# BottomSide.net
KiCad netlist of a schematic drawn in Altium Designer
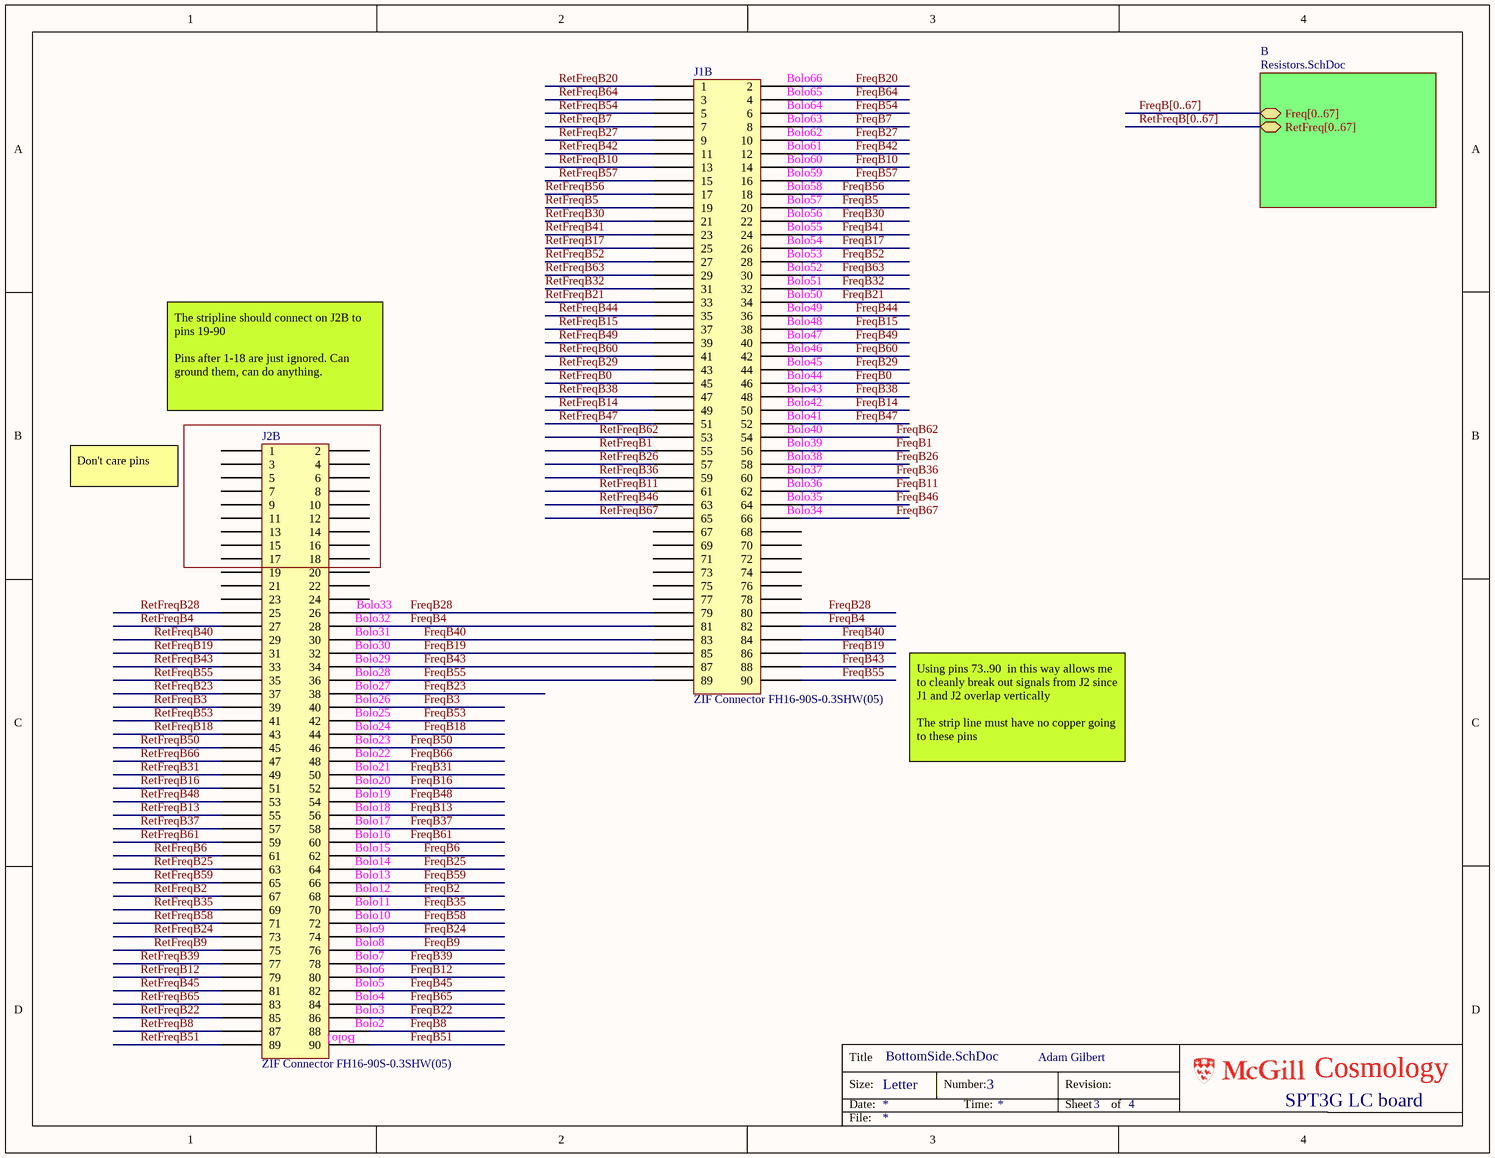
[diagram p0: BottomSide.SchDoc]

(export (version "E")
  (design (tool "Eeschema 10.0.6"))
  (components
    (comp (ref "J1B")
      (value "ZIF Connector FH16-90S-0.3SHW(05)")
      (footprint "LCBoard_ZIFCon")
      (libsource (lib "SPT3G_LCBoard") (part "LCboard_FH16-90S-0.3SHW(05)"))
    )
    (comp (ref "J2B")
      (value "ZIF Connector FH16-90S-0.3SHW(05)")
      (footprint "LCBoard_ZIFCon")
      (libsource (lib "SPT3G_LCBoard") (part "LCboard_FH16-90S-0.3SHW(05)"))
    )
  )
  (nets
    (net (code "5") (name "/FreqB0") (class "Default")
      (node (ref "J1B") (pin "46") (pinfunction "46_46") (pintype "passive"))
    )
    (net (code "6") (name "/FreqB1") (class "Default")
      (node (ref "J1B") (pin "56") (pinfunction "56_56") (pintype "passive"))
    )
    (net (code "7") (name "/FreqB2") (class "Default")
      (node (ref "J2B") (pin "68") (pinfunction "68_68") (pintype "passive"))
    )
    (net (code "8") (name "/FreqB3") (class "Default")
      (node (ref "J2B") (pin "40") (pinfunction "40_40") (pintype "passive"))
    )
    (net (code "9") (name "/FreqB4") (class "Default")
      (node (ref "J1B") (pin "81") (pinfunction "81_81") (pintype "passive"))
      (node (ref "J1B") (pin "82") (pinfunction "82_82") (pintype "passive"))
      (node (ref "J2B") (pin "28") (pinfunction "28_28") (pintype "passive"))
    )
    (net (code "10") (name "/FreqB5") (class "Default")
      (node (ref "J1B") (pin "20") (pinfunction "20_20") (pintype "passive"))
    )
    (net (code "11") (name "/FreqB6") (class "Default")
      (node (ref "J2B") (pin "62") (pinfunction "62_62") (pintype "passive"))
    )
    (net (code "12") (name "/FreqB7") (class "Default")
      (node (ref "J1B") (pin "8") (pinfunction "8_8") (pintype "passive"))
    )
    (net (code "13") (name "/FreqB8") (class "Default")
      (node (ref "J2B") (pin "88") (pinfunction "88_88") (pintype "passive"))
    )
    (net (code "14") (name "/FreqB9") (class "Default")
      (node (ref "J2B") (pin "76") (pinfunction "76_76") (pintype "passive"))
    )
    (net (code "15") (name "/FreqB10") (class "Default")
      (node (ref "J1B") (pin "14") (pinfunction "14_14") (pintype "passive"))
    )
    (net (code "16") (name "/FreqB11") (class "Default")
      (node (ref "J1B") (pin "62") (pinfunction "62_62") (pintype "passive"))
    )
    (net (code "17") (name "/FreqB12") (class "Default")
      (node (ref "J2B") (pin "80") (pinfunction "80_80") (pintype "passive"))
    )
    (net (code "18") (name "/FreqB13") (class "Default")
      (node (ref "J2B") (pin "56") (pinfunction "56_56") (pintype "passive"))
    )
    (net (code "19") (name "/FreqB14") (class "Default")
      (node (ref "J1B") (pin "50") (pinfunction "50_50") (pintype "passive"))
    )
    (net (code "20") (name "/FreqB15") (class "Default")
      (node (ref "J1B") (pin "38") (pinfunction "38_38") (pintype "passive"))
    )
    (net (code "21") (name "/FreqB16") (class "Default")
      (node (ref "J2B") (pin "52") (pinfunction "52_52") (pintype "passive"))
    )
    (net (code "22") (name "/FreqB17") (class "Default")
      (node (ref "J1B") (pin "26") (pinfunction "26_26") (pintype "passive"))
    )
    (net (code "23") (name "/FreqB18") (class "Default")
      (node (ref "J2B") (pin "44") (pinfunction "44_44") (pintype "passive"))
    )
    (net (code "24") (name "/FreqB19") (class "Default")
      (node (ref "J1B") (pin "85") (pinfunction "85_85") (pintype "passive"))
      (node (ref "J1B") (pin "86") (pinfunction "86_86") (pintype "passive"))
      (node (ref "J2B") (pin "32") (pinfunction "32_32") (pintype "passive"))
    )
    (net (code "25") (name "/FreqB20") (class "Default")
      (node (ref "J1B") (pin "2") (pinfunction "2_2") (pintype "passive"))
    )
    (net (code "26") (name "/FreqB21") (class "Default")
      (node (ref "J1B") (pin "34") (pinfunction "34_34") (pintype "passive"))
    )
    (net (code "27") (name "/FreqB22") (class "Default")
      (node (ref "J2B") (pin "86") (pinfunction "86_86") (pintype "passive"))
    )
    (net (code "28") (name "/FreqB23") (class "Default")
      (node (ref "J2B") (pin "38") (pinfunction "38_38") (pintype "passive"))
    )
    (net (code "29") (name "/FreqB24") (class "Default")
      (node (ref "J2B") (pin "74") (pinfunction "74_74") (pintype "passive"))
    )
    (net (code "30") (name "/FreqB25") (class "Default")
      (node (ref "J2B") (pin "64") (pinfunction "64_64") (pintype "passive"))
    )
    (net (code "31") (name "/FreqB26") (class "Default")
      (node (ref "J1B") (pin "58") (pinfunction "58_58") (pintype "passive"))
    )
    (net (code "32") (name "/FreqB27") (class "Default")
      (node (ref "J1B") (pin "10") (pinfunction "10_10") (pintype "passive"))
    )
    (net (code "33") (name "/FreqB28") (class "Default")
      (node (ref "J1B") (pin "79") (pinfunction "79_79") (pintype "passive"))
      (node (ref "J1B") (pin "80") (pinfunction "80_80") (pintype "passive"))
      (node (ref "J2B") (pin "26") (pinfunction "26_26") (pintype "passive"))
    )
    (net (code "34") (name "/FreqB29") (class "Default")
      (node (ref "J1B") (pin "44") (pinfunction "44_44") (pintype "passive"))
    )
    (net (code "35") (name "/FreqB30") (class "Default")
      (node (ref "J1B") (pin "22") (pinfunction "22_22") (pintype "passive"))
    )
    (net (code "36") (name "/FreqB31") (class "Default")
      (node (ref "J2B") (pin "50") (pinfunction "50_50") (pintype "passive"))
    )
    (net (code "37") (name "/FreqB32") (class "Default")
      (node (ref "J1B") (pin "32") (pinfunction "32_32") (pintype "passive"))
    )
    (net (code "38") (name "/FreqB35") (class "Default")
      (node (ref "J2B") (pin "70") (pinfunction "70_70") (pintype "passive"))
    )
    (net (code "39") (name "/FreqB36") (class "Default")
      (node (ref "J1B") (pin "60") (pinfunction "60_60") (pintype "passive"))
    )
    (net (code "40") (name "/FreqB37") (class "Default")
      (node (ref "J2B") (pin "58") (pinfunction "58_58") (pintype "passive"))
    )
    (net (code "41") (name "/FreqB38") (class "Default")
      (node (ref "J1B") (pin "48") (pinfunction "48_48") (pintype "passive"))
    )
    (net (code "42") (name "/FreqB39") (class "Default")
      (node (ref "J2B") (pin "78") (pinfunction "78_78") (pintype "passive"))
    )
    (net (code "43") (name "/FreqB40") (class "Default")
      (node (ref "J1B") (pin "83") (pinfunction "83_83") (pintype "passive"))
      (node (ref "J1B") (pin "84") (pinfunction "84_84") (pintype "passive"))
      (node (ref "J2B") (pin "30") (pinfunction "30_30") (pintype "passive"))
    )
    (net (code "44") (name "/FreqB41") (class "Default")
      (node (ref "J1B") (pin "24") (pinfunction "24_24") (pintype "passive"))
    )
    (net (code "45") (name "/FreqB42") (class "Default")
      (node (ref "J1B") (pin "12") (pinfunction "12_12") (pintype "passive"))
    )
    (net (code "46") (name "/FreqB43") (class "Default")
      (node (ref "J1B") (pin "87") (pinfunction "87_87") (pintype "passive"))
      (node (ref "J1B") (pin "88") (pinfunction "88_88") (pintype "passive"))
      (node (ref "J2B") (pin "34") (pinfunction "34_34") (pintype "passive"))
    )
    (net (code "47") (name "/FreqB44") (class "Default")
      (node (ref "J1B") (pin "36") (pinfunction "36_36") (pintype "passive"))
    )
    (net (code "48") (name "/FreqB45") (class "Default")
      (node (ref "J2B") (pin "82") (pinfunction "82_82") (pintype "passive"))
    )
    (net (code "49") (name "/FreqB46") (class "Default")
      (node (ref "J1B") (pin "64") (pinfunction "64_64") (pintype "passive"))
    )
    (net (code "50") (name "/FreqB47") (class "Default")
      (node (ref "J1B") (pin "52") (pinfunction "52_52") (pintype "passive"))
    )
    (net (code "51") (name "/FreqB48") (class "Default")
      (node (ref "J2B") (pin "54") (pinfunction "54_54") (pintype "passive"))
    )
    (net (code "52") (name "/FreqB49") (class "Default")
      (node (ref "J1B") (pin "40") (pinfunction "40_40") (pintype "passive"))
    )
    (net (code "53") (name "/FreqB50") (class "Default")
      (node (ref "J2B") (pin "46") (pinfunction "46_46") (pintype "passive"))
    )
    (net (code "54") (name "/FreqB51") (class "Default")
      (node (ref "J2B") (pin "90") (pinfunction "90_90") (pintype "passive"))
    )
    (net (code "55") (name "/FreqB52") (class "Default")
      (node (ref "J1B") (pin "28") (pinfunction "28_28") (pintype "passive"))
    )
    (net (code "56") (name "/FreqB53") (class "Default")
      (node (ref "J2B") (pin "42") (pinfunction "42_42") (pintype "passive"))
    )
    (net (code "57") (name "/FreqB54") (class "Default")
      (node (ref "J1B") (pin "6") (pinfunction "6_6") (pintype "passive"))
    )
    (net (code "58") (name "/FreqB55") (class "Default")
      (node (ref "J1B") (pin "89") (pinfunction "89_89") (pintype "passive"))
      (node (ref "J1B") (pin "90") (pinfunction "90_90") (pintype "passive"))
      (node (ref "J2B") (pin "36") (pinfunction "36_36") (pintype "passive"))
    )
    (net (code "59") (name "/FreqB56") (class "Default")
      (node (ref "J1B") (pin "18") (pinfunction "18_18") (pintype "passive"))
    )
    (net (code "60") (name "/FreqB57") (class "Default")
      (node (ref "J1B") (pin "16") (pinfunction "16_16") (pintype "passive"))
    )
    (net (code "61") (name "/FreqB58") (class "Default")
      (node (ref "J2B") (pin "72") (pinfunction "72_72") (pintype "passive"))
    )
    (net (code "62") (name "/FreqB59") (class "Default")
      (node (ref "J2B") (pin "66") (pinfunction "66_66") (pintype "passive"))
    )
    (net (code "63") (name "/FreqB60") (class "Default")
      (node (ref "J1B") (pin "42") (pinfunction "42_42") (pintype "passive"))
    )
    (net (code "64") (name "/FreqB61") (class "Default")
      (node (ref "J2B") (pin "60") (pinfunction "60_60") (pintype "passive"))
    )
    (net (code "65") (name "/FreqB62") (class "Default")
      (node (ref "J1B") (pin "54") (pinfunction "54_54") (pintype "passive"))
    )
    (net (code "66") (name "/FreqB63") (class "Default")
      (node (ref "J1B") (pin "30") (pinfunction "30_30") (pintype "passive"))
    )
    (net (code "67") (name "/FreqB64") (class "Default")
      (node (ref "J1B") (pin "4") (pinfunction "4_4") (pintype "passive"))
    )
    (net (code "68") (name "/FreqB65") (class "Default")
      (node (ref "J2B") (pin "84") (pinfunction "84_84") (pintype "passive"))
    )
    (net (code "69") (name "/FreqB66") (class "Default")
      (node (ref "J2B") (pin "48") (pinfunction "48_48") (pintype "passive"))
    )
    (net (code "70") (name "/FreqB67") (class "Default")
      (node (ref "J1B") (pin "66") (pinfunction "66_66") (pintype "passive"))
    )
    (net (code "72") (name "/RetFreqB0") (class "Default")
      (node (ref "J1B") (pin "45") (pinfunction "45_45") (pintype "passive"))
    )
    (net (code "73") (name "/RetFreqB1") (class "Default")
      (node (ref "J1B") (pin "55") (pinfunction "55_55") (pintype "passive"))
    )
    (net (code "74") (name "/RetFreqB2") (class "Default")
      (node (ref "J2B") (pin "67") (pinfunction "67_67") (pintype "passive"))
    )
    (net (code "75") (name "/RetFreqB3") (class "Default")
      (node (ref "J2B") (pin "39") (pinfunction "39_39") (pintype "passive"))
    )
    (net (code "76") (name "/RetFreqB4") (class "Default")
      (node (ref "J2B") (pin "27") (pinfunction "27_27") (pintype "passive"))
    )
    (net (code "77") (name "/RetFreqB5") (class "Default")
      (node (ref "J1B") (pin "19") (pinfunction "19_19") (pintype "passive"))
    )
    (net (code "78") (name "/RetFreqB6") (class "Default")
      (node (ref "J2B") (pin "61") (pinfunction "61_61") (pintype "passive"))
    )
    (net (code "79") (name "/RetFreqB7") (class "Default")
      (node (ref "J1B") (pin "7") (pinfunction "7_7") (pintype "passive"))
    )
    (net (code "80") (name "/RetFreqB8") (class "Default")
      (node (ref "J2B") (pin "87") (pinfunction "87_87") (pintype "passive"))
    )
    (net (code "81") (name "/RetFreqB9") (class "Default")
      (node (ref "J2B") (pin "75") (pinfunction "75_75") (pintype "passive"))
    )
    (net (code "82") (name "/RetFreqB10") (class "Default")
      (node (ref "J1B") (pin "13") (pinfunction "13_13") (pintype "passive"))
    )
    (net (code "83") (name "/RetFreqB11") (class "Default")
      (node (ref "J1B") (pin "61") (pinfunction "61_61") (pintype "passive"))
    )
    (net (code "84") (name "/RetFreqB12") (class "Default")
      (node (ref "J2B") (pin "79") (pinfunction "79_79") (pintype "passive"))
    )
    (net (code "85") (name "/RetFreqB13") (class "Default")
      (node (ref "J2B") (pin "55") (pinfunction "55_55") (pintype "passive"))
    )
    (net (code "86") (name "/RetFreqB14") (class "Default")
      (node (ref "J1B") (pin "49") (pinfunction "49_49") (pintype "passive"))
    )
    (net (code "87") (name "/RetFreqB15") (class "Default")
      (node (ref "J1B") (pin "37") (pinfunction "37_37") (pintype "passive"))
    )
    (net (code "88") (name "/RetFreqB16") (class "Default")
      (node (ref "J2B") (pin "51") (pinfunction "51_51") (pintype "passive"))
    )
    (net (code "89") (name "/RetFreqB17") (class "Default")
      (node (ref "J1B") (pin "25") (pinfunction "25_25") (pintype "passive"))
    )
    (net (code "90") (name "/RetFreqB18") (class "Default")
      (node (ref "J2B") (pin "43") (pinfunction "43_43") (pintype "passive"))
    )
    (net (code "91") (name "/RetFreqB19") (class "Default")
      (node (ref "J2B") (pin "31") (pinfunction "31_31") (pintype "passive"))
    )
    (net (code "92") (name "/RetFreqB20") (class "Default")
      (node (ref "J1B") (pin "1") (pinfunction "1_1") (pintype "passive"))
    )
    (net (code "93") (name "/RetFreqB21") (class "Default")
      (node (ref "J1B") (pin "33") (pinfunction "33_33") (pintype "passive"))
    )
    (net (code "94") (name "/RetFreqB22") (class "Default")
      (node (ref "J2B") (pin "85") (pinfunction "85_85") (pintype "passive"))
    )
    (net (code "95") (name "/RetFreqB23") (class "Default")
      (node (ref "J2B") (pin "37") (pinfunction "37_37") (pintype "passive"))
    )
    (net (code "96") (name "/RetFreqB24") (class "Default")
      (node (ref "J2B") (pin "73") (pinfunction "73_73") (pintype "passive"))
    )
    (net (code "97") (name "/RetFreqB25") (class "Default")
      (node (ref "J2B") (pin "63") (pinfunction "63_63") (pintype "passive"))
    )
    (net (code "98") (name "/RetFreqB26") (class "Default")
      (node (ref "J1B") (pin "57") (pinfunction "57_57") (pintype "passive"))
    )
    (net (code "99") (name "/RetFreqB27") (class "Default")
      (node (ref "J1B") (pin "9") (pinfunction "9_9") (pintype "passive"))
    )
    (net (code "100") (name "/RetFreqB28") (class "Default")
      (node (ref "J2B") (pin "25") (pinfunction "25_25") (pintype "passive"))
    )
    (net (code "101") (name "/RetFreqB29") (class "Default")
      (node (ref "J1B") (pin "43") (pinfunction "43_43") (pintype "passive"))
    )
    (net (code "102") (name "/RetFreqB30") (class "Default")
      (node (ref "J1B") (pin "21") (pinfunction "21_21") (pintype "passive"))
    )
    (net (code "103") (name "/RetFreqB31") (class "Default")
      (node (ref "J2B") (pin "49") (pinfunction "49_49") (pintype "passive"))
    )
    (net (code "104") (name "/RetFreqB32") (class "Default")
      (node (ref "J1B") (pin "31") (pinfunction "31_31") (pintype "passive"))
    )
    (net (code "105") (name "/RetFreqB35") (class "Default")
      (node (ref "J2B") (pin "69") (pinfunction "69_69") (pintype "passive"))
    )
    (net (code "106") (name "/RetFreqB36") (class "Default")
      (node (ref "J1B") (pin "59") (pinfunction "59_59") (pintype "passive"))
    )
    (net (code "107") (name "/RetFreqB37") (class "Default")
      (node (ref "J2B") (pin "57") (pinfunction "57_57") (pintype "passive"))
    )
    (net (code "108") (name "/RetFreqB38") (class "Default")
      (node (ref "J1B") (pin "47") (pinfunction "47_47") (pintype "passive"))
    )
    (net (code "109") (name "/RetFreqB39") (class "Default")
      (node (ref "J2B") (pin "77") (pinfunction "77_77") (pintype "passive"))
    )
    (net (code "110") (name "/RetFreqB40") (class "Default")
      (node (ref "J2B") (pin "29") (pinfunction "29_29") (pintype "passive"))
    )
    (net (code "111") (name "/RetFreqB41") (class "Default")
      (node (ref "J1B") (pin "23") (pinfunction "23_23") (pintype "passive"))
    )
    (net (code "112") (name "/RetFreqB42") (class "Default")
      (node (ref "J1B") (pin "11") (pinfunction "11_11") (pintype "passive"))
    )
    (net (code "113") (name "/RetFreqB43") (class "Default")
      (node (ref "J2B") (pin "33") (pinfunction "33_33") (pintype "passive"))
    )
    (net (code "114") (name "/RetFreqB44") (class "Default")
      (node (ref "J1B") (pin "35") (pinfunction "35_35") (pintype "passive"))
    )
    (net (code "115") (name "/RetFreqB45") (class "Default")
      (node (ref "J2B") (pin "81") (pinfunction "81_81") (pintype "passive"))
    )
    (net (code "116") (name "/RetFreqB46") (class "Default")
      (node (ref "J1B") (pin "63") (pinfunction "63_63") (pintype "passive"))
    )
    (net (code "117") (name "/RetFreqB47") (class "Default")
      (node (ref "J1B") (pin "51") (pinfunction "51_51") (pintype "passive"))
    )
    (net (code "118") (name "/RetFreqB48") (class "Default")
      (node (ref "J2B") (pin "53") (pinfunction "53_53") (pintype "passive"))
    )
    (net (code "119") (name "/RetFreqB49") (class "Default")
      (node (ref "J1B") (pin "39") (pinfunction "39_39") (pintype "passive"))
    )
    (net (code "120") (name "/RetFreqB50") (class "Default")
      (node (ref "J2B") (pin "45") (pinfunction "45_45") (pintype "passive"))
    )
    (net (code "121") (name "/RetFreqB51") (class "Default")
      (node (ref "J2B") (pin "89") (pinfunction "89_89") (pintype "passive"))
    )
    (net (code "122") (name "/RetFreqB52") (class "Default")
      (node (ref "J1B") (pin "27") (pinfunction "27_27") (pintype "passive"))
    )
    (net (code "123") (name "/RetFreqB53") (class "Default")
      (node (ref "J2B") (pin "41") (pinfunction "41_41") (pintype "passive"))
    )
    (net (code "124") (name "/RetFreqB54") (class "Default")
      (node (ref "J1B") (pin "5") (pinfunction "5_5") (pintype "passive"))
    )
    (net (code "125") (name "/RetFreqB55") (class "Default")
      (node (ref "J2B") (pin "35") (pinfunction "35_35") (pintype "passive"))
    )
    (net (code "126") (name "/RetFreqB56") (class "Default")
      (node (ref "J1B") (pin "17") (pinfunction "17_17") (pintype "passive"))
    )
    (net (code "127") (name "/RetFreqB57") (class "Default")
      (node (ref "J1B") (pin "15") (pinfunction "15_15") (pintype "passive"))
    )
    (net (code "128") (name "/RetFreqB58") (class "Default")
      (node (ref "J2B") (pin "71") (pinfunction "71_71") (pintype "passive"))
    )
    (net (code "129") (name "/RetFreqB59") (class "Default")
      (node (ref "J2B") (pin "65") (pinfunction "65_65") (pintype "passive"))
    )
    (net (code "130") (name "/RetFreqB60") (class "Default")
      (node (ref "J1B") (pin "41") (pinfunction "41_41") (pintype "passive"))
    )
    (net (code "131") (name "/RetFreqB61") (class "Default")
      (node (ref "J2B") (pin "59") (pinfunction "59_59") (pintype "passive"))
    )
    (net (code "132") (name "/RetFreqB62") (class "Default")
      (node (ref "J1B") (pin "53") (pinfunction "53_53") (pintype "passive"))
    )
    (net (code "133") (name "/RetFreqB63") (class "Default")
      (node (ref "J1B") (pin "29") (pinfunction "29_29") (pintype "passive"))
    )
    (net (code "134") (name "/RetFreqB64") (class "Default")
      (node (ref "J1B") (pin "3") (pinfunction "3_3") (pintype "passive"))
    )
    (net (code "135") (name "/RetFreqB65") (class "Default")
      (node (ref "J2B") (pin "83") (pinfunction "83_83") (pintype "passive"))
    )
    (net (code "136") (name "/RetFreqB66") (class "Default")
      (node (ref "J2B") (pin "47") (pinfunction "47_47") (pintype "passive"))
    )
    (net (code "137") (name "/RetFreqB67") (class "Default")
      (node (ref "J1B") (pin "65") (pinfunction "65_65") (pintype "passive"))
    )
    (net (code "139") (name "unconnected-(J1B-Pad67)") (class "Default")
      (node (ref "J1B") (pin "67") (pinfunction "67_67") (pintype "passive"))
    )
    (net (code "140") (name "unconnected-(J1B-Pad68)") (class "Default")
      (node (ref "J1B") (pin "68") (pinfunction "68_68") (pintype "passive"))
    )
    (net (code "141") (name "unconnected-(J1B-Pad69)") (class "Default")
      (node (ref "J1B") (pin "69") (pinfunction "69_69") (pintype "passive"))
    )
    (net (code "142") (name "unconnected-(J1B-Pad70)") (class "Default")
      (node (ref "J1B") (pin "70") (pinfunction "70_70") (pintype "passive"))
    )
    (net (code "143") (name "unconnected-(J1B-Pad71)") (class "Default")
      (node (ref "J1B") (pin "71") (pinfunction "71_71") (pintype "passive"))
    )
    (net (code "144") (name "unconnected-(J1B-Pad72)") (class "Default")
      (node (ref "J1B") (pin "72") (pinfunction "72_72") (pintype "passive"))
    )
    (net (code "145") (name "unconnected-(J1B-Pad73)") (class "Default")
      (node (ref "J1B") (pin "73") (pinfunction "73_73") (pintype "passive"))
    )
    (net (code "146") (name "unconnected-(J1B-Pad74)") (class "Default")
      (node (ref "J1B") (pin "74") (pinfunction "74_74") (pintype "passive"))
    )
    (net (code "147") (name "unconnected-(J1B-Pad75)") (class "Default")
      (node (ref "J1B") (pin "75") (pinfunction "75_75") (pintype "passive"))
    )
    (net (code "148") (name "unconnected-(J1B-Pad76)") (class "Default")
      (node (ref "J1B") (pin "76") (pinfunction "76_76") (pintype "passive"))
    )
    (net (code "149") (name "unconnected-(J1B-Pad77)") (class "Default")
      (node (ref "J1B") (pin "77") (pinfunction "77_77") (pintype "passive"))
    )
    (net (code "150") (name "unconnected-(J1B-Pad78)") (class "Default")
      (node (ref "J1B") (pin "78") (pinfunction "78_78") (pintype "passive"))
    )
    (net (code "151") (name "unconnected-(J2B-Pad1)") (class "Default")
      (node (ref "J2B") (pin "1") (pinfunction "1_1") (pintype "passive"))
    )
    (net (code "152") (name "unconnected-(J2B-Pad2)") (class "Default")
      (node (ref "J2B") (pin "2") (pinfunction "2_2") (pintype "passive"))
    )
    (net (code "153") (name "unconnected-(J2B-Pad3)") (class "Default")
      (node (ref "J2B") (pin "3") (pinfunction "3_3") (pintype "passive"))
    )
    (net (code "154") (name "unconnected-(J2B-Pad4)") (class "Default")
      (node (ref "J2B") (pin "4") (pinfunction "4_4") (pintype "passive"))
    )
    (net (code "155") (name "unconnected-(J2B-Pad5)") (class "Default")
      (node (ref "J2B") (pin "5") (pinfunction "5_5") (pintype "passive"))
    )
    (net (code "156") (name "unconnected-(J2B-Pad6)") (class "Default")
      (node (ref "J2B") (pin "6") (pinfunction "6_6") (pintype "passive"))
    )
    (net (code "157") (name "unconnected-(J2B-Pad7)") (class "Default")
      (node (ref "J2B") (pin "7") (pinfunction "7_7") (pintype "passive"))
    )
    (net (code "158") (name "unconnected-(J2B-Pad8)") (class "Default")
      (node (ref "J2B") (pin "8") (pinfunction "8_8") (pintype "passive"))
    )
    (net (code "159") (name "unconnected-(J2B-Pad9)") (class "Default")
      (node (ref "J2B") (pin "9") (pinfunction "9_9") (pintype "passive"))
    )
    (net (code "160") (name "unconnected-(J2B-Pad10)") (class "Default")
      (node (ref "J2B") (pin "10") (pinfunction "10_10") (pintype "passive"))
    )
    (net (code "161") (name "unconnected-(J2B-Pad11)") (class "Default")
      (node (ref "J2B") (pin "11") (pinfunction "11_11") (pintype "passive"))
    )
    (net (code "162") (name "unconnected-(J2B-Pad12)") (class "Default")
      (node (ref "J2B") (pin "12") (pinfunction "12_12") (pintype "passive"))
    )
    (net (code "163") (name "unconnected-(J2B-Pad13)") (class "Default")
      (node (ref "J2B") (pin "13") (pinfunction "13_13") (pintype "passive"))
    )
    (net (code "164") (name "unconnected-(J2B-Pad14)") (class "Default")
      (node (ref "J2B") (pin "14") (pinfunction "14_14") (pintype "passive"))
    )
    (net (code "165") (name "unconnected-(J2B-Pad15)") (class "Default")
      (node (ref "J2B") (pin "15") (pinfunction "15_15") (pintype "passive"))
    )
    (net (code "166") (name "unconnected-(J2B-Pad16)") (class "Default")
      (node (ref "J2B") (pin "16") (pinfunction "16_16") (pintype "passive"))
    )
    (net (code "167") (name "unconnected-(J2B-Pad17)") (class "Default")
      (node (ref "J2B") (pin "17") (pinfunction "17_17") (pintype "passive"))
    )
    (net (code "168") (name "unconnected-(J2B-Pad18)") (class "Default")
      (node (ref "J2B") (pin "18") (pinfunction "18_18") (pintype "passive"))
    )
    (net (code "169") (name "unconnected-(J2B-Pad19)") (class "Default")
      (node (ref "J2B") (pin "19") (pinfunction "19_19") (pintype "passive"))
    )
    (net (code "170") (name "unconnected-(J2B-Pad20)") (class "Default")
      (node (ref "J2B") (pin "20") (pinfunction "20_20") (pintype "passive"))
    )
    (net (code "171") (name "unconnected-(J2B-Pad21)") (class "Default")
      (node (ref "J2B") (pin "21") (pinfunction "21_21") (pintype "passive"))
    )
    (net (code "172") (name "unconnected-(J2B-Pad22)") (class "Default")
      (node (ref "J2B") (pin "22") (pinfunction "22_22") (pintype "passive"))
    )
    (net (code "173") (name "unconnected-(J2B-Pad23)") (class "Default")
      (node (ref "J2B") (pin "23") (pinfunction "23_23") (pintype "passive"))
    )
    (net (code "174") (name "unconnected-(J2B-Pad24)") (class "Default")
      (node (ref "J2B") (pin "24") (pinfunction "24_24") (pintype "passive"))
    )
  )
)
